# -5v_Reg_biggr.net
KiCad netlist of a schematic drawn in Altium Designer
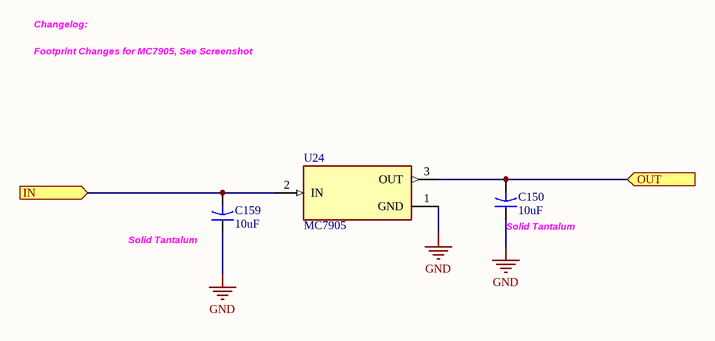
[diagram p0: -5v_Reg_biggr.SchDoc]

(export (version "E")
  (design (tool "Eeschema 10.0.6"))
  (components
    (comp (ref "C150")
      (value "10uF")
      (footprint "Tantalum_2917")
      (description "Capacitor, 100uF NICHICON")
      (libsource (lib "Arturo_Approved") (part "UVR1V102MHD1TO"))
    )
    (comp (ref "C159")
      (value "10uF")
      (footprint "Tantalum_2917")
      (description "Capacitor, 100uF NICHICON")
      (libsource (lib "Arturo_Approved") (part "UVR1V102MHD1TO"))
    )
    (comp (ref "U24")
      (value "MC7905")
      (footprint "MC7905")
      (libsource (lib "Arturo_Approved") (part "MC7905"))
    )
  )
  (nets
    (net (code "1") (name "/IN") (class "Default")
      (node (ref "C159") (pin "2") (pinfunction "2_2") (pintype "passive"))
      (node (ref "U24") (pin "2") (pinfunction "IN_2") (pintype "input"))
    )
    (net (code "2") (name "/OUT") (class "Default")
      (node (ref "C150") (pin "2") (pinfunction "2_2") (pintype "passive"))
      (node (ref "U24") (pin "3") (pinfunction "OUT_3") (pintype "output"))
    )
    (net (code "3") (name "GND") (class "Default")
      (node (ref "C150") (pin "1") (pinfunction "1_1") (pintype "passive"))
      (node (ref "C159") (pin "1") (pinfunction "1_1") (pintype "passive"))
      (node (ref "U24") (pin "1") (pinfunction "GND_1") (pintype "power_in"))
    )
  )
)
